# Time_Base.net
KiCad netlist of a schematic drawn in Altium Designer
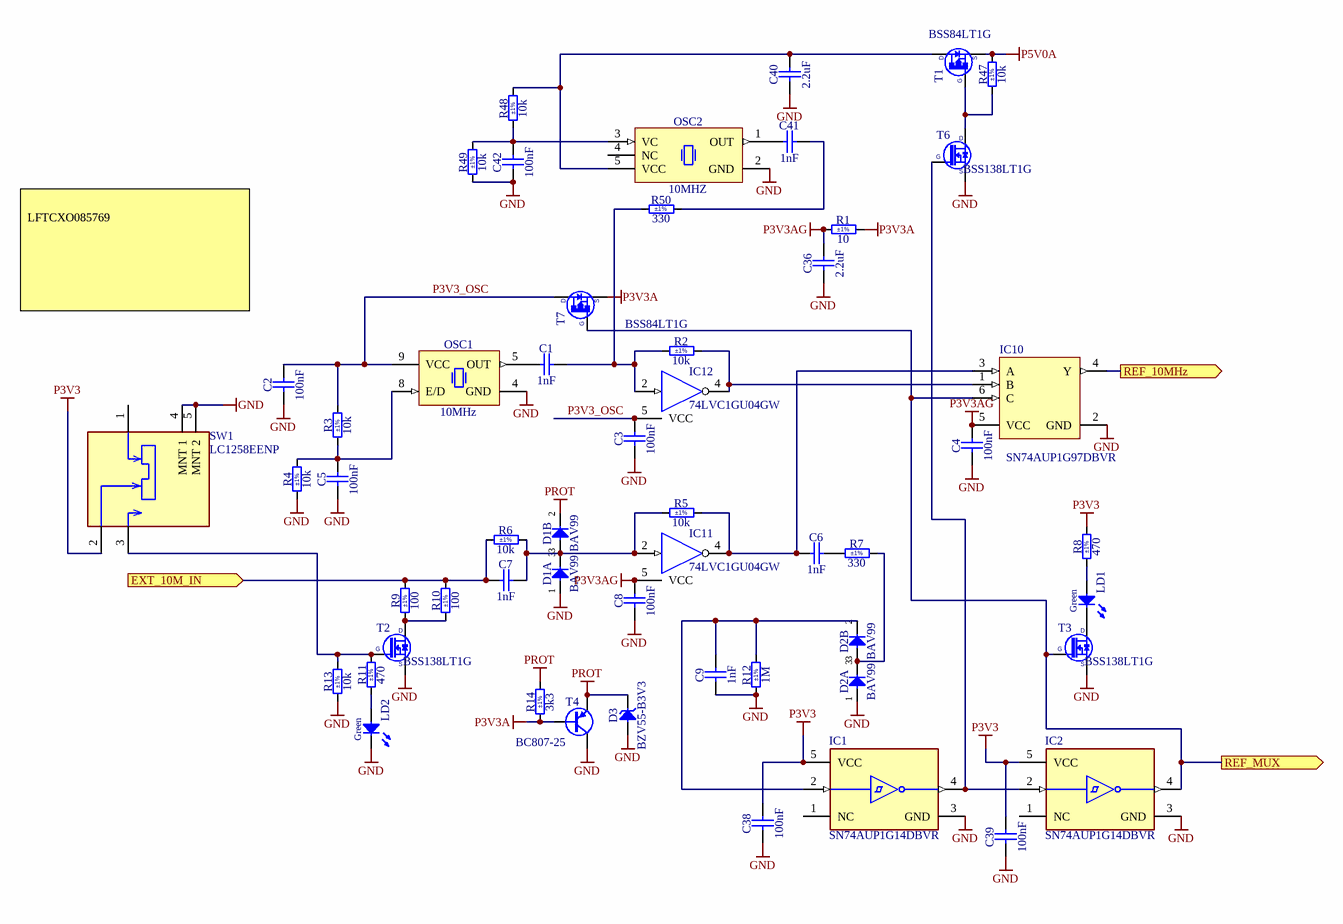
[diagram p0: Time_Base.SchDoc]

(export (version "E")
  (design (tool "Eeschema 10.0.6"))
  (components
    (comp (ref "C1")
      (value "1nF")
      (footprint "CAPC1608X90N")
      (description "Non-polarised capacitor")
      (fields
        (field (name "PART NUMBER") "CC0603_1NF_50V_1%_NP0")
        (field (name "VOLTAGE") "50V")
        (field (name "AUTHOR") "CERN DEM JLC")
      )
      (libsource (lib "Capacitors") (part "Capacitor - non polarized"))
    )
    (comp (ref "C2")
      (value "100nF")
      (footprint "CAPC1608X90N")
      (description "Non-polarised capacitor")
      (fields
        (field (name "PART NUMBER") "CC0603_100NF_100V_10%_X7R")
        (field (name "VOLTAGE") "100V")
        (field (name "AUTHOR") "CERN DEM JLC")
      )
      (libsource (lib "Capacitors") (part "Capacitor - non polarized"))
    )
    (comp (ref "C3")
      (value "100nF")
      (footprint "CAPC1608X90N")
      (description "Non-polarised capacitor")
      (fields
        (field (name "PART NUMBER") "CC0603_100NF_100V_10%_X7R")
        (field (name "VOLTAGE") "100V")
        (field (name "AUTHOR") "CERN DEM JLC")
      )
      (libsource (lib "Capacitors") (part "Capacitor - non polarized"))
    )
    (comp (ref "C4")
      (value "100nF")
      (footprint "CAPC1608X90N")
      (description "Non-polarised capacitor")
      (fields
        (field (name "PART NUMBER") "CC0603_100NF_100V_10%_X7R")
        (field (name "VOLTAGE") "100V")
        (field (name "AUTHOR") "CERN DEM JLC")
      )
      (libsource (lib "Capacitors") (part "Capacitor - non polarized"))
    )
    (comp (ref "C5")
      (value "100nF")
      (footprint "CAPC1608X90N")
      (description "Non-polarised capacitor")
      (fields
        (field (name "PART NUMBER") "CC0603_100NF_100V_10%_X7R")
        (field (name "VOLTAGE") "100V")
        (field (name "AUTHOR") "CERN DEM JLC")
      )
      (libsource (lib "Capacitors") (part "Capacitor - non polarized"))
    )
    (comp (ref "C6")
      (value "1nF")
      (footprint "CAPC1608X90N")
      (description "Non-polarised capacitor")
      (fields
        (field (name "PART NUMBER") "CC0603_1NF_50V_1%_NP0")
        (field (name "VOLTAGE") "50V")
        (field (name "AUTHOR") "CERN DEM JLC")
      )
      (libsource (lib "Capacitors") (part "Capacitor - non polarized"))
    )
    (comp (ref "C7")
      (value "1nF")
      (footprint "CAPC1608X90N")
      (description "Non-polarised capacitor")
      (fields
        (field (name "PART NUMBER") "CC0603_1NF_50V_1%_NP0")
        (field (name "VOLTAGE") "50V")
        (field (name "AUTHOR") "CERN DEM JLC")
      )
      (libsource (lib "Capacitors") (part "Capacitor - non polarized"))
    )
    (comp (ref "C8")
      (value "100nF")
      (footprint "CAPC1608X90N")
      (description "Non-polarised capacitor")
      (fields
        (field (name "PART NUMBER") "CC0603_100NF_100V_10%_X7R")
        (field (name "VOLTAGE") "100V")
        (field (name "AUTHOR") "CERN DEM JLC")
      )
      (libsource (lib "Capacitors") (part "Capacitor - non polarized"))
    )
    (comp (ref "C9")
      (value "1nF")
      (footprint "CAPC1608X90N")
      (description "Non-polarised capacitor")
      (fields
        (field (name "PART NUMBER") "CC0603_1NF_50V_1%_NP0")
        (field (name "VOLTAGE") "50V")
        (field (name "AUTHOR") "CERN DEM JLC")
      )
      (libsource (lib "Capacitors") (part "Capacitor - non polarized"))
    )
    (comp (ref "C36")
      (value "2.2uF")
      (footprint "CAPC1608X90N")
      (description "Non-polarised capacitor")
      (fields
        (field (name "PART NUMBER") "CC0603_2.2UF_10V_20%_X7R")
        (field (name "VOLTAGE") "10V")
        (field (name "AUTHOR") "CERN DEM JLC")
      )
      (libsource (lib "Capacitors") (part "Capacitor - non polarized"))
    )
    (comp (ref "C38")
      (value "100nF")
      (footprint "CAPC1608X90N")
      (description "Non-polarised capacitor")
      (fields
        (field (name "PART NUMBER") "CC0603_100NF_100V_10%_X7R")
        (field (name "VOLTAGE") "100V")
        (field (name "AUTHOR") "CERN DEM JLC")
      )
      (libsource (lib "Capacitors") (part "Capacitor - non polarized"))
    )
    (comp (ref "C39")
      (value "100nF")
      (footprint "CAPC1608X90N")
      (description "Non-polarised capacitor")
      (fields
        (field (name "PART NUMBER") "CC0603_100NF_100V_10%_X7R")
        (field (name "VOLTAGE") "100V")
        (field (name "AUTHOR") "CERN DEM JLC")
      )
      (libsource (lib "Capacitors") (part "Capacitor - non polarized"))
    )
    (comp (ref "C40")
      (value "2.2uF")
      (footprint "CAPC1608X90N")
      (description "Non-polarised capacitor")
      (fields
        (field (name "PART NUMBER") "CC0603_2.2UF_10V_20%_X7R")
        (field (name "VOLTAGE") "10V")
        (field (name "AUTHOR") "CERN DEM JLC")
      )
      (libsource (lib "Capacitors") (part "Capacitor - non polarized"))
    )
    (comp (ref "C41")
      (value "1nF")
      (footprint "CAPC1608X90N")
      (description "Non-polarised capacitor")
      (fields
        (field (name "PART NUMBER") "CC0603_1NF_50V_1%_NP0")
        (field (name "VOLTAGE") "50V")
        (field (name "AUTHOR") "CERN DEM JLC")
      )
      (libsource (lib "Capacitors") (part "Capacitor - non polarized"))
    )
    (comp (ref "C42")
      (value "100nF")
      (footprint "CAPC1608X90N")
      (description "Non-polarised capacitor")
      (fields
        (field (name "PART NUMBER") "CC0603_100NF_100V_10%_X7R")
        (field (name "VOLTAGE") "100V")
        (field (name "AUTHOR") "CERN DEM JLC")
      )
      (libsource (lib "Capacitors") (part "Capacitor - non polarized"))
    )
    (comp (ref "D1")
      (value "BAV99")
      (footprint "SOT95P240X110-3N")
      (description "Serial Diode")
      (fields
        (field (name "VOLTAGE") "70V")
        (field (name "POWER") "350mW")
        (field (name "AUTHOR") "CERN DEM JLC")
      )
      (libsource (lib "ICs And Semiconductors") (part "Diode x2 A1C3_A3C2"))
    )
    (comp (ref "D2")
      (value "BAV99")
      (footprint "SOT95P240X110-3N")
      (description "Serial Diode")
      (fields
        (field (name "VOLTAGE") "70V")
        (field (name "POWER") "350mW")
        (field (name "AUTHOR") "CERN DEM JLC")
      )
      (libsource (lib "ICs And Semiconductors") (part "Diode x2 A1C3_A3C2"))
    )
    (comp (ref "D3")
      (value "BZV55-B3V3")
      (footprint "DIOMELF3515N")
      (description "Zener Diode")
      (fields
        (field (name "VOLTAGE") "3V3")
        (field (name "POWER") "500mW")
        (field (name "AUTHOR") "CERN DEM JLC")
      )
      (libsource (lib "ICs And Semiconductors") (part "Diode Zener"))
    )
    (comp (ref "IC1")
      (value "SN74AUP1G14DBVR")
      (footprint "FP-DBV0005A-IPC_A")
      (description "IC INVERTER SCHMITT 1CH SOT23-5")
      (libsource (lib "Altium Content Vault") (part "d7d47fafed669226aeca1918140c228"))
    )
    (comp (ref "IC2")
      (value "SN74AUP1G14DBVR")
      (footprint "FP-DBV0005A-IPC_A")
      (description "IC INVERTER SCHMITT 1CH SOT23-5")
      (libsource (lib "Altium Content Vault") (part "d7d47fafed669226aeca1918140c228"))
    )
    (comp (ref "IC10")
      (value "SN74AUP1G97DBVR")
      (footprint "DBV0006A_L")
      (description "Low-Power Configurable Multiple-Function Gate, DBV0006A, LARGE T&R")
      (fields
        (field (name "GENERIC PART NUMBER") "SN74AUP1G97")
        (field (name "MANUFACTURER") "Texas Instruments")
      )
      (libsource (lib "Altium Content Vault") (part "TI-SN74AUP1G97-6"))
    )
    (comp (ref "IC11")
      (value "74LVC1GU04GW")
      (footprint "SOT65P212X110-5N")
      (description "Single Inverter Buffer")
      (fields (field (name "MANUFACTURER") "NXP SEMICONDUCTORS") (field (name "AUTHOR") "CERN DEM JLC"))
      (libsource (lib "ICs And Semiconductors") (part "741G04"))
    )
    (comp (ref "IC12")
      (value "74LVC1GU04GW")
      (footprint "SOT65P212X110-5N")
      (description "Single Inverter Buffer")
      (fields (field (name "MANUFACTURER") "NXP SEMICONDUCTORS") (field (name "AUTHOR") "CERN DEM JLC"))
      (libsource (lib "ICs And Semiconductors") (part "741G04"))
    )
    (comp (ref "LD1")
      (value "Green")
      (footprint "LED_AVAGO_HSME-C110")
      (description "LED Green 1C 2A")
      (fields
        (field (name "PART NUMBER") "LED_AVAGO_HSME-C110")
        (field (name "MANUFACTURER") "AVAGO TECHNOLOGIES")
        (field (name "AUTHOR") "CERN DEM JMW")
      )
      (libsource (lib "ICs And Semiconductors") (part "LED Green 1C 2A"))
    )
    (comp (ref "LD2")
      (value "Green")
      (footprint "LED_AVAGO_HSME-C110")
      (description "LED Green 1C 2A")
      (fields
        (field (name "PART NUMBER") "LED_AVAGO_HSME-C110")
        (field (name "MANUFACTURER") "AVAGO TECHNOLOGIES")
        (field (name "AUTHOR") "CERN DEM JMW")
      )
      (libsource (lib "ICs And Semiconductors") (part "LED Green 1C 2A"))
    )
    (comp (ref "OSC1")
      (value "10MHz")
      (footprint "OSC_CONNOR-WINFIELD_D75")
      (description "Oscillator 4 pins 4=GND 5=OUT 8=E/D 9=VCC")
      (fields
        (field (name "PART NUMBER") "OSC_10MHZ_CONNOR-WINFIELD_D75A-010.0M")
        (field (name "MANUFACTURER") "CONNOR-WINFIELD")
        (field (name "AUTHOR") "CERN DEM JLC")
      )
      (libsource (lib "ICs And Semiconductors") (part "Oscillator 4GND 5OUT 8E/D 9VCC"))
    )
    (comp (ref "OSC2")
      (value "10MHZ")
      (footprint "OSC_CONNOR-WINFIELD_OH100")
      (description "STRATUM 3E High Stability Oven Stabilized Oscillator, VCOCXO (OH100 Series)")
      (fields
        (field (name "PART NUMBER") "OSC_10MHZ_CONNOR-WINFIELD_OH100-71003SV")
        (field (name "MANUFACTURER") "CONNOR-WINFIELD")
        (field (name "AUTHOR") "CERN DEM BC")
      )
      (libsource (lib "ICs And Semiconductors") (part "Oscillator CONNOR-WINFIELD_OH100-VC"))
    )
    (comp (ref "R1")
      (value "10")
      (footprint "RESC1608X55N")
      (description "Resistor - 1%")
      (fields
        (field (name "TOLERANCE") "±1%")
        (field (name "PART NUMBER") "R0603_10R_1%_0.1W_100PPM")
        (field (name "POWER") "0.1W")
        (field (name "AUTHOR") "CERN DEM HF")
      )
      (libsource (lib "Resistors") (part "Resistor - 1%"))
    )
    (comp (ref "R2")
      (value "10k")
      (footprint "RESC1608X55N")
      (description "Resistor - 1%")
      (fields
        (field (name "TOLERANCE") "±1%")
        (field (name "PART NUMBER") "R0603_10K_1%_0.1W_100PPM")
        (field (name "POWER") "0.1W")
        (field (name "AUTHOR") "CERN DEM JLC")
      )
      (libsource (lib "Resistors") (part "Resistor - 1%"))
    )
    (comp (ref "R3")
      (value "10k")
      (footprint "RESC1608X55N")
      (description "Resistor - 1%")
      (fields
        (field (name "TOLERANCE") "±1%")
        (field (name "PART NUMBER") "R0603_10K_1%_0.1W_100PPM")
        (field (name "POWER") "0.1W")
        (field (name "AUTHOR") "CERN DEM JLC")
      )
      (libsource (lib "Resistors") (part "Resistor - 1%"))
    )
    (comp (ref "R4")
      (value "10k")
      (footprint "RESC1608X55N")
      (description "Resistor - 1%")
      (fields
        (field (name "TOLERANCE") "±1%")
        (field (name "PART NUMBER") "R0603_10K_1%_0.1W_100PPM")
        (field (name "POWER") "0.1W")
        (field (name "AUTHOR") "CERN DEM JLC")
      )
      (libsource (lib "Resistors") (part "Resistor - 1%"))
    )
    (comp (ref "R5")
      (value "10k")
      (footprint "RESC1608X55N")
      (description "Resistor - 1%")
      (fields
        (field (name "TOLERANCE") "±1%")
        (field (name "PART NUMBER") "R0603_10K_1%_0.1W_100PPM")
        (field (name "POWER") "0.1W")
        (field (name "AUTHOR") "CERN DEM JLC")
      )
      (libsource (lib "Resistors") (part "Resistor - 1%"))
    )
    (comp (ref "R6")
      (value "10k")
      (footprint "RESC1608X55N")
      (description "Resistor - 1%")
      (fields
        (field (name "TOLERANCE") "±1%")
        (field (name "PART NUMBER") "R0603_10K_1%_0.1W_100PPM")
        (field (name "POWER") "0.1W")
        (field (name "AUTHOR") "CERN DEM JLC")
      )
      (libsource (lib "Resistors") (part "Resistor - 1%"))
    )
    (comp (ref "R7")
      (value "330")
      (footprint "RESC1608X55N")
      (description "Resistor - 1%")
      (fields
        (field (name "TOLERANCE") "±1%")
        (field (name "PART NUMBER") "R0603_330R_1%_0.1W_100PPM")
        (field (name "POWER") "0.1W")
        (field (name "AUTHOR") "CERN DEM JLC")
      )
      (libsource (lib "Resistors") (part "Resistor - 1%"))
    )
    (comp (ref "R8")
      (value "470")
      (footprint "RESC1608X55N")
      (description "Resistor - 1%")
      (fields
        (field (name "TOLERANCE") "±1%")
        (field (name "PART NUMBER") "R0603_470R_1%_0.1W_100PPM")
        (field (name "POWER") "0.1W")
        (field (name "AUTHOR") "CERN DEM JLC")
      )
      (libsource (lib "Resistors") (part "Resistor - 1%"))
    )
    (comp (ref "R9")
      (value "100")
      (footprint "RESC1608X55N")
      (description "Resistor - 1%")
      (fields
        (field (name "TOLERANCE") "±1%")
        (field (name "PART NUMBER") "R0603_100R_1%_0.1W_100PPM")
        (field (name "POWER") "0.1W")
        (field (name "AUTHOR") "CERN DEM JLC")
      )
      (libsource (lib "Resistors") (part "Resistor - 1%"))
    )
    (comp (ref "R10")
      (value "100")
      (footprint "RESC1608X55N")
      (description "Resistor - 1%")
      (fields
        (field (name "TOLERANCE") "±1%")
        (field (name "PART NUMBER") "R0603_100R_1%_0.1W_100PPM")
        (field (name "POWER") "0.1W")
        (field (name "AUTHOR") "CERN DEM JLC")
      )
      (libsource (lib "Resistors") (part "Resistor - 1%"))
    )
    (comp (ref "R11")
      (value "470")
      (footprint "RESC1608X55N")
      (description "Resistor - 1%")
      (fields
        (field (name "TOLERANCE") "±1%")
        (field (name "PART NUMBER") "R0603_470R_1%_0.1W_100PPM")
        (field (name "POWER") "0.1W")
        (field (name "AUTHOR") "CERN DEM JLC")
      )
      (libsource (lib "Resistors") (part "Resistor - 1%"))
    )
    (comp (ref "R12")
      (value "1M")
      (footprint "RESC1608X55N")
      (description "Resistor - 1%")
      (fields
        (field (name "TOLERANCE") "±1%")
        (field (name "PART NUMBER") "R0603_1M_1%_0.1W_100PPM")
        (field (name "POWER") "0.1W")
        (field (name "AUTHOR") "CERN DEM JLC")
      )
      (libsource (lib "Resistors") (part "Resistor - 1%"))
    )
    (comp (ref "R13")
      (value "10k")
      (footprint "RESC1608X55N")
      (description "Resistor - 1%")
      (fields
        (field (name "TOLERANCE") "±1%")
        (field (name "PART NUMBER") "R0603_10K_1%_0.1W_100PPM")
        (field (name "POWER") "0.1W")
        (field (name "AUTHOR") "CERN DEM JLC")
      )
      (libsource (lib "Resistors") (part "Resistor - 1%"))
    )
    (comp (ref "R14")
      (value "3k3")
      (footprint "RESC1608X55N")
      (description "Resistor - 1%")
      (fields
        (field (name "TOLERANCE") "±1%")
        (field (name "PART NUMBER") "R0603_3K3_1%_0.1W_100PPM")
        (field (name "POWER") "0.1W")
        (field (name "AUTHOR") "CERN DEM JLC")
      )
      (libsource (lib "Resistors") (part "Resistor - 1%"))
    )
    (comp (ref "R47")
      (value "10k")
      (footprint "RESC1608X55N")
      (description "Resistor - 1%")
      (fields
        (field (name "TOLERANCE") "±1%")
        (field (name "PART NUMBER") "R0603_10K_1%_0.1W_100PPM")
        (field (name "POWER") "0.1W")
        (field (name "AUTHOR") "CERN DEM JLC")
      )
      (libsource (lib "Resistors") (part "Resistor - 1%"))
    )
    (comp (ref "R48")
      (value "10k")
      (footprint "RESC1608X55N")
      (description "Resistor - 1%")
      (fields
        (field (name "TOLERANCE") "±1%")
        (field (name "PART NUMBER") "R0603_10K_1%_0.1W_100PPM")
        (field (name "POWER") "0.1W")
        (field (name "AUTHOR") "CERN DEM JLC")
      )
      (libsource (lib "Resistors") (part "Resistor - 1%"))
    )
    (comp (ref "R49")
      (value "10k")
      (footprint "RESC1608X55N")
      (description "Resistor - 1%")
      (fields
        (field (name "TOLERANCE") "±1%")
        (field (name "PART NUMBER") "R0603_10K_1%_0.1W_100PPM")
        (field (name "POWER") "0.1W")
        (field (name "AUTHOR") "CERN DEM JLC")
      )
      (libsource (lib "Resistors") (part "Resistor - 1%"))
    )
    (comp (ref "R50")
      (value "330")
      (footprint "RESC1608X55N")
      (description "Resistor - 1%")
      (fields
        (field (name "TOLERANCE") "±1%")
        (field (name "PART NUMBER") "R0603_330R_1%_0.1W_100PPM")
        (field (name "POWER") "0.1W")
        (field (name "AUTHOR") "CERN DEM JLC")
      )
      (libsource (lib "Resistors") (part "Resistor - 1%"))
    )
    (comp (ref "SW1")
      (value "LC1258EENP")
      (footprint "FP-LC1258EENP-MFG")
      (description "SWITCH PUSHBUTTON SPDT 0.3A 30V")
      (fields
        (field (name "OCTOPART") "https://octopart.com/lc1258eenp-e-switch-1061525")
        (field (name "MANUFACTURER") "E-Switch")
      )
      (libsource (lib "Altium Content Vault") (part "0508c39cd0da6f0d1ad8893551ea0e6"))
    )
    (comp (ref "T1")
      (value "BSS84LT1G")
      (footprint "SOT95P240X110-3N")
      (description "P-CHANNEL MOSFET WITH DIODE")
      (fields
        (field (name "MANUFACTURER") "ON SEMICONDUCTOR")
        (field (name "MANUFACTURER PART NUMBER") "BSS84L")
        (field (name "AUTHOR") "CERN DEM JLC")
      )
      (libsource (lib "ICs And Semiconductors") (part "P-MOSFET-D 1G 2S 3D"))
    )
    (comp (ref "T2")
      (value "BSS138LT1G")
      (footprint "SOT95P240X110-3N")
      (description "N-CHANNEL MOSFET WITH DIODE")
      (fields
        (field (name "MANUFACTURER") "ON SEMICONDUCTOR")
        (field (name "MANUFACTURER PART NUMBER") "BSS138L")
        (field (name "AUTHOR") "CERN DEM JLC")
      )
      (libsource (lib "ICs And Semiconductors") (part "N-MOSFET-D 1G 2S 3D"))
    )
    (comp (ref "T3")
      (value "BSS138LT1G")
      (footprint "SOT95P240X110-3N")
      (description "N-CHANNEL MOSFET WITH DIODE")
      (fields
        (field (name "MANUFACTURER") "ON SEMICONDUCTOR")
        (field (name "MANUFACTURER PART NUMBER") "BSS138L")
        (field (name "AUTHOR") "CERN DEM JLC")
      )
      (libsource (lib "ICs And Semiconductors") (part "N-MOSFET-D 1G 2S 3D"))
    )
    (comp (ref "T4")
      (value "BC807-25")
      (footprint "SOT95P230X110-3N")
      (description "PNP Transistor")
      (fields (field (name "MANUFACTURER") "NXP SEMICONDUCTORS") (field (name "AUTHOR") "CERN DEM JLC"))
      (libsource (lib "ICs And Semiconductors") (part "PNP B1 E2 C3"))
    )
    (comp (ref "T6")
      (value "BSS138LT1G")
      (footprint "SOT95P240X110-3N")
      (description "N-CHANNEL MOSFET WITH DIODE")
      (fields
        (field (name "MANUFACTURER") "ON SEMICONDUCTOR")
        (field (name "MANUFACTURER PART NUMBER") "BSS138L")
        (field (name "AUTHOR") "CERN DEM JLC")
      )
      (libsource (lib "ICs And Semiconductors") (part "N-MOSFET-D 1G 2S 3D"))
    )
    (comp (ref "T7")
      (value "BSS84LT1G")
      (footprint "SOT95P240X110-3N")
      (description "P-CHANNEL MOSFET WITH DIODE")
      (fields
        (field (name "MANUFACTURER") "ON SEMICONDUCTOR")
        (field (name "MANUFACTURER PART NUMBER") "BSS84L")
        (field (name "AUTHOR") "CERN DEM JLC")
      )
      (libsource (lib "ICs And Semiconductors") (part "P-MOSFET-D 1G 2S 3D"))
    )
  )
  (nets
    (net (code "1") (name "/EXT_10M_IN") (class "Default")
      (node (ref "C7") (pin "1") (pinfunction "1_1") (pintype "passive"))
      (node (ref "R10") (pin "2") (pinfunction "2_2") (pintype "passive"))
      (node (ref "R6") (pin "1") (pinfunction "1_1") (pintype "passive"))
      (node (ref "R9") (pin "2") (pinfunction "2_2") (pintype "passive"))
    )
    (net (code "2") (name "/P3V3_OSC") (class "Default")
      (node (ref "C2") (pin "2") (pinfunction "2_2") (pintype "passive"))
      (node (ref "C3") (pin "2") (pinfunction "2_2") (pintype "passive"))
      (node (ref "IC12") (pin "5") (pinfunction "VCC_5") (pintype "power_in"))
      (node (ref "OSC1") (pin "9") (pinfunction "VCC_9") (pintype "power_in"))
      (node (ref "R3") (pin "2") (pinfunction "2_2") (pintype "passive"))
      (node (ref "T7") (pin "3") (pinfunction "D_3") (pintype "passive"))
    )
    (net (code "3") (name "/REF_10MHz") (class "Default")
      (node (ref "IC10") (pin "4") (pinfunction "Y_4") (pintype "output"))
    )
    (net (code "4") (name "/REF_MUX") (class "Default")
      (node (ref "IC10") (pin "6") (pinfunction "C_6") (pintype "input"))
      (node (ref "IC2") (pin "4") (pinfunction "Y_4") (pintype "output"))
      (node (ref "T3") (pin "1") (pinfunction "G_1") (pintype "passive"))
      (node (ref "T7") (pin "1") (pinfunction "G_1") (pintype "passive"))
    )
    (net (code "5") (name "GND") (class "Default")
      (node (ref "C2") (pin "1") (pinfunction "1_1") (pintype "passive"))
      (node (ref "C3") (pin "1") (pinfunction "1_1") (pintype "passive"))
      (node (ref "C36") (pin "1") (pinfunction "1_1") (pintype "passive"))
      (node (ref "C38") (pin "1") (pinfunction "1_1") (pintype "passive"))
      (node (ref "C39") (pin "1") (pinfunction "1_1") (pintype "passive"))
      (node (ref "C4") (pin "1") (pinfunction "1_1") (pintype "passive"))
      (node (ref "C40") (pin "1") (pinfunction "1_1") (pintype "passive"))
      (node (ref "C42") (pin "1") (pinfunction "1_1") (pintype "passive"))
      (node (ref "C5") (pin "1") (pinfunction "1_1") (pintype "passive"))
      (node (ref "C8") (pin "1") (pinfunction "1_1") (pintype "passive"))
      (node (ref "C9") (pin "1") (pinfunction "1_1") (pintype "passive"))
      (node (ref "D1") (pin "1") (pinfunction "A_1") (pintype "passive"))
      (node (ref "D2") (pin "1") (pinfunction "A_1") (pintype "passive"))
      (node (ref "D3") (pin "2") (pinfunction "A_2") (pintype "passive"))
      (node (ref "IC1") (pin "3") (pinfunction "GND_3") (pintype "power_in"))
      (node (ref "IC10") (pin "2") (pinfunction "GND_2") (pintype "power_in"))
      (node (ref "IC11") (pin "3") (pinfunction "GND_3") (pintype "power_in"))
      (node (ref "IC12") (pin "3") (pinfunction "GND_3") (pintype "power_in"))
      (node (ref "IC2") (pin "3") (pinfunction "GND_3") (pintype "power_in"))
      (node (ref "LD2") (pin "1") (pinfunction "C_1") (pintype "passive"))
      (node (ref "OSC1") (pin "4") (pinfunction "GND_4") (pintype "power_in"))
      (node (ref "OSC2") (pin "2") (pinfunction "GND_2") (pintype "power_in"))
      (node (ref "R12") (pin "1") (pinfunction "1_1") (pintype "passive"))
      (node (ref "R13") (pin "1") (pinfunction "1_1") (pintype "passive"))
      (node (ref "R4") (pin "1") (pinfunction "1_1") (pintype "passive"))
      (node (ref "R49") (pin "1") (pinfunction "1_1") (pintype "passive"))
      (node (ref "SW1") (pin "4") (pinfunction "MNT_1_4") (pintype "passive"))
      (node (ref "SW1") (pin "5") (pinfunction "MNT_2_5") (pintype "passive"))
      (node (ref "T2") (pin "2") (pinfunction "S_2") (pintype "passive"))
      (node (ref "T3") (pin "2") (pinfunction "S_2") (pintype "passive"))
      (node (ref "T4") (pin "3") (pinfunction "C_3") (pintype "passive"))
      (node (ref "T6") (pin "2") (pinfunction "S_2") (pintype "passive"))
    )
    (net (code "6") (name "Net-(C6-Pad2)") (class "Default")
      (node (ref "C6") (pin "2") (pinfunction "2_2") (pintype "passive"))
      (node (ref "R7") (pin "1") (pinfunction "1_1") (pintype "passive"))
    )
    (net (code "7") (name "Net-(C41-Pad2)") (class "Default")
      (node (ref "C41") (pin "2") (pinfunction "2_2") (pintype "passive"))
      (node (ref "R50") (pin "2") (pinfunction "2_2") (pintype "passive"))
    )
    (net (code "8") (name "Net-(D1A-COMAC)") (class "Default")
      (node (ref "C7") (pin "2") (pinfunction "2_2") (pintype "passive"))
      (node (ref "D1") (pin "3") (pinfunction "COMAC_3") (pintype "passive"))
      (node (ref "IC11") (pin "2") (pinfunction "IN_2") (pintype "input"))
      (node (ref "R5") (pin "1") (pinfunction "1_1") (pintype "passive"))
      (node (ref "R6") (pin "2") (pinfunction "2_2") (pintype "passive"))
    )
    (net (code "9") (name "Net-(D2A-COMAC)") (class "Default")
      (node (ref "D2") (pin "3") (pinfunction "COMAC_3") (pintype "passive"))
      (node (ref "R7") (pin "2") (pinfunction "2_2") (pintype "passive"))
    )
    (net (code "10") (name "Net-(D2B-C)") (class "Default")
      (node (ref "C9") (pin "2") (pinfunction "2_2") (pintype "passive"))
      (node (ref "D2") (pin "2") (pinfunction "C_2") (pintype "passive"))
      (node (ref "IC1") (pin "2") (pinfunction "A_2") (pintype "input"))
      (node (ref "R12") (pin "2") (pinfunction "2_2") (pintype "passive"))
    )
    (net (code "11") (name "Net-(IC1-Y)") (class "Default")
      (node (ref "IC1") (pin "4") (pinfunction "Y_4") (pintype "output"))
      (node (ref "IC2") (pin "2") (pinfunction "A_2") (pintype "input"))
      (node (ref "T6") (pin "1") (pinfunction "G_1") (pintype "passive"))
    )
    (net (code "12") (name "Net-(IC10-A)") (class "Default")
      (node (ref "C6") (pin "1") (pinfunction "1_1") (pintype "passive"))
      (node (ref "IC10") (pin "3") (pinfunction "A_3") (pintype "input"))
      (node (ref "IC11") (pin "4") (pinfunction "OUT_4") (pintype "open_collector"))
      (node (ref "R5") (pin "2") (pinfunction "2_2") (pintype "passive"))
    )
    (net (code "13") (name "Net-(IC10-B)") (class "Default")
      (node (ref "IC10") (pin "1") (pinfunction "B_1") (pintype "input"))
      (node (ref "IC12") (pin "4") (pinfunction "OUT_4") (pintype "open_collector"))
      (node (ref "R2") (pin "2") (pinfunction "2_2") (pintype "passive"))
    )
    (net (code "14") (name "Net-(IC12-IN)") (class "Default")
      (node (ref "C1") (pin "2") (pinfunction "2_2") (pintype "passive"))
      (node (ref "IC12") (pin "2") (pinfunction "IN_2") (pintype "input"))
      (node (ref "R2") (pin "1") (pinfunction "1_1") (pintype "passive"))
      (node (ref "R50") (pin "1") (pinfunction "1_1") (pintype "passive"))
    )
    (net (code "15") (name "Net-(LD1-A)") (class "Default")
      (node (ref "LD1") (pin "2") (pinfunction "A_2") (pintype "passive"))
      (node (ref "R8") (pin "1") (pinfunction "1_1") (pintype "passive"))
    )
    (net (code "16") (name "Net-(LD1-C)") (class "Default")
      (node (ref "LD1") (pin "1") (pinfunction "C_1") (pintype "passive"))
      (node (ref "T3") (pin "3") (pinfunction "D_3") (pintype "passive"))
    )
    (net (code "17") (name "Net-(LD2-A)") (class "Default")
      (node (ref "LD2") (pin "2") (pinfunction "A_2") (pintype "passive"))
      (node (ref "R11") (pin "1") (pinfunction "1_1") (pintype "passive"))
    )
    (net (code "18") (name "Net-(OSC1-E{slash}D)") (class "Default")
      (node (ref "C5") (pin "2") (pinfunction "2_2") (pintype "passive"))
      (node (ref "OSC1") (pin "8") (pinfunction "E/D_8") (pintype "input"))
      (node (ref "R3") (pin "1") (pinfunction "1_1") (pintype "passive"))
      (node (ref "R4") (pin "2") (pinfunction "2_2") (pintype "passive"))
    )
    (net (code "19") (name "Net-(OSC1-OUT)") (class "Default")
      (node (ref "C1") (pin "1") (pinfunction "1_1") (pintype "passive"))
      (node (ref "OSC1") (pin "5") (pinfunction "OUT_5") (pintype "output"))
    )
    (net (code "20") (name "Net-(OSC2-OUT)") (class "Default")
      (node (ref "C41") (pin "1") (pinfunction "1_1") (pintype "passive"))
      (node (ref "OSC2") (pin "1") (pinfunction "OUT_1") (pintype "output"))
    )
    (net (code "21") (name "Net-(OSC2-VC)") (class "Default")
      (node (ref "C42") (pin "2") (pinfunction "2_2") (pintype "passive"))
      (node (ref "OSC2") (pin "3") (pinfunction "VC_3") (pintype "input"))
      (node (ref "R48") (pin "1") (pinfunction "1_1") (pintype "passive"))
      (node (ref "R49") (pin "2") (pinfunction "2_2") (pintype "passive"))
    )
    (net (code "22") (name "Net-(OSC2-VCC)") (class "Default")
      (node (ref "C40") (pin "2") (pinfunction "2_2") (pintype "passive"))
      (node (ref "OSC2") (pin "5") (pinfunction "VCC_5") (pintype "power_in"))
      (node (ref "R48") (pin "2") (pinfunction "2_2") (pintype "passive"))
      (node (ref "T1") (pin "3") (pinfunction "D_3") (pintype "passive"))
    )
    (net (code "23") (name "Net-(T1-G)") (class "Default")
      (node (ref "R47") (pin "1") (pinfunction "1_1") (pintype "passive"))
      (node (ref "T1") (pin "1") (pinfunction "G_1") (pintype "passive"))
      (node (ref "T6") (pin "3") (pinfunction "D_3") (pintype "passive"))
    )
    (net (code "24") (name "Net-(T2-D)") (class "Default")
      (node (ref "R10") (pin "1") (pinfunction "1_1") (pintype "passive"))
      (node (ref "R9") (pin "1") (pinfunction "1_1") (pintype "passive"))
      (node (ref "T2") (pin "3") (pinfunction "D_3") (pintype "passive"))
    )
    (net (code "25") (name "Net-(T2-G)") (class "Default")
      (node (ref "R11") (pin "2") (pinfunction "2_2") (pintype "passive"))
      (node (ref "R13") (pin "2") (pinfunction "2_2") (pintype "passive"))
      (node (ref "SW1") (pin "3") (pinfunction "3_3") (pintype "passive"))
      (node (ref "T2") (pin "1") (pinfunction "G_1") (pintype "passive"))
    )
    (net (code "26") (name "P3V3") (class "Default")
      (node (ref "C38") (pin "2") (pinfunction "2_2") (pintype "passive"))
      (node (ref "C39") (pin "2") (pinfunction "2_2") (pintype "passive"))
      (node (ref "IC1") (pin "5") (pinfunction "VCC_5") (pintype "power_in"))
      (node (ref "IC2") (pin "5") (pinfunction "VCC_5") (pintype "power_in"))
      (node (ref "R8") (pin "2") (pinfunction "2_2") (pintype "passive"))
      (node (ref "SW1") (pin "2") (pinfunction "2_2") (pintype "passive"))
    )
    (net (code "27") (name "P3V3A") (class "Default")
      (node (ref "R1") (pin "2") (pinfunction "2_2") (pintype "passive"))
      (node (ref "R14") (pin "1") (pinfunction "1_1") (pintype "passive"))
      (node (ref "T4") (pin "1") (pinfunction "B_1") (pintype "passive"))
      (node (ref "T7") (pin "2") (pinfunction "S_2") (pintype "passive"))
    )
    (net (code "28") (name "P3V3AG") (class "Default")
      (node (ref "C36") (pin "2") (pinfunction "2_2") (pintype "passive"))
      (node (ref "C4") (pin "2") (pinfunction "2_2") (pintype "passive"))
      (node (ref "C8") (pin "2") (pinfunction "2_2") (pintype "passive"))
      (node (ref "IC10") (pin "5") (pinfunction "VCC_5") (pintype "power_in"))
      (node (ref "IC11") (pin "5") (pinfunction "VCC_5") (pintype "power_in"))
      (node (ref "R1") (pin "1") (pinfunction "1_1") (pintype "passive"))
    )
    (net (code "29") (name "P5V0A") (class "Default")
      (node (ref "R47") (pin "2") (pinfunction "2_2") (pintype "passive"))
      (node (ref "T1") (pin "2") (pinfunction "S_2") (pintype "passive"))
    )
    (net (code "30") (name "PROT") (class "Default")
      (node (ref "D1") (pin "2") (pinfunction "C_2") (pintype "passive"))
      (node (ref "D3") (pin "1") (pinfunction "C_1") (pintype "passive"))
      (node (ref "R14") (pin "2") (pinfunction "2_2") (pintype "passive"))
      (node (ref "T4") (pin "2") (pinfunction "E_2") (pintype "passive"))
    )
    (net (code "31") (name "unconnected-(IC1-NC-Pad1)") (class "Default")
      (node (ref "IC1") (pin "1") (pinfunction "NC_1") (pintype "passive"))
    )
    (net (code "32") (name "unconnected-(IC2-NC-Pad1)") (class "Default")
      (node (ref "IC2") (pin "1") (pinfunction "NC_1") (pintype "passive"))
    )
    (net (code "33") (name "unconnected-(OSC2-NC-Pad4)") (class "Default")
      (node (ref "OSC2") (pin "4") (pinfunction "NC_4") (pintype "passive"))
    )
    (net (code "34") (name "unconnected-(SW1-Pad1)") (class "Default")
      (node (ref "SW1") (pin "1") (pinfunction "1_1") (pintype "passive"))
    )
  )
)
